# SCH_n2_power_distribution_board-png_2022.net
KiCad netlist of a schematic drawn in EasyEDA
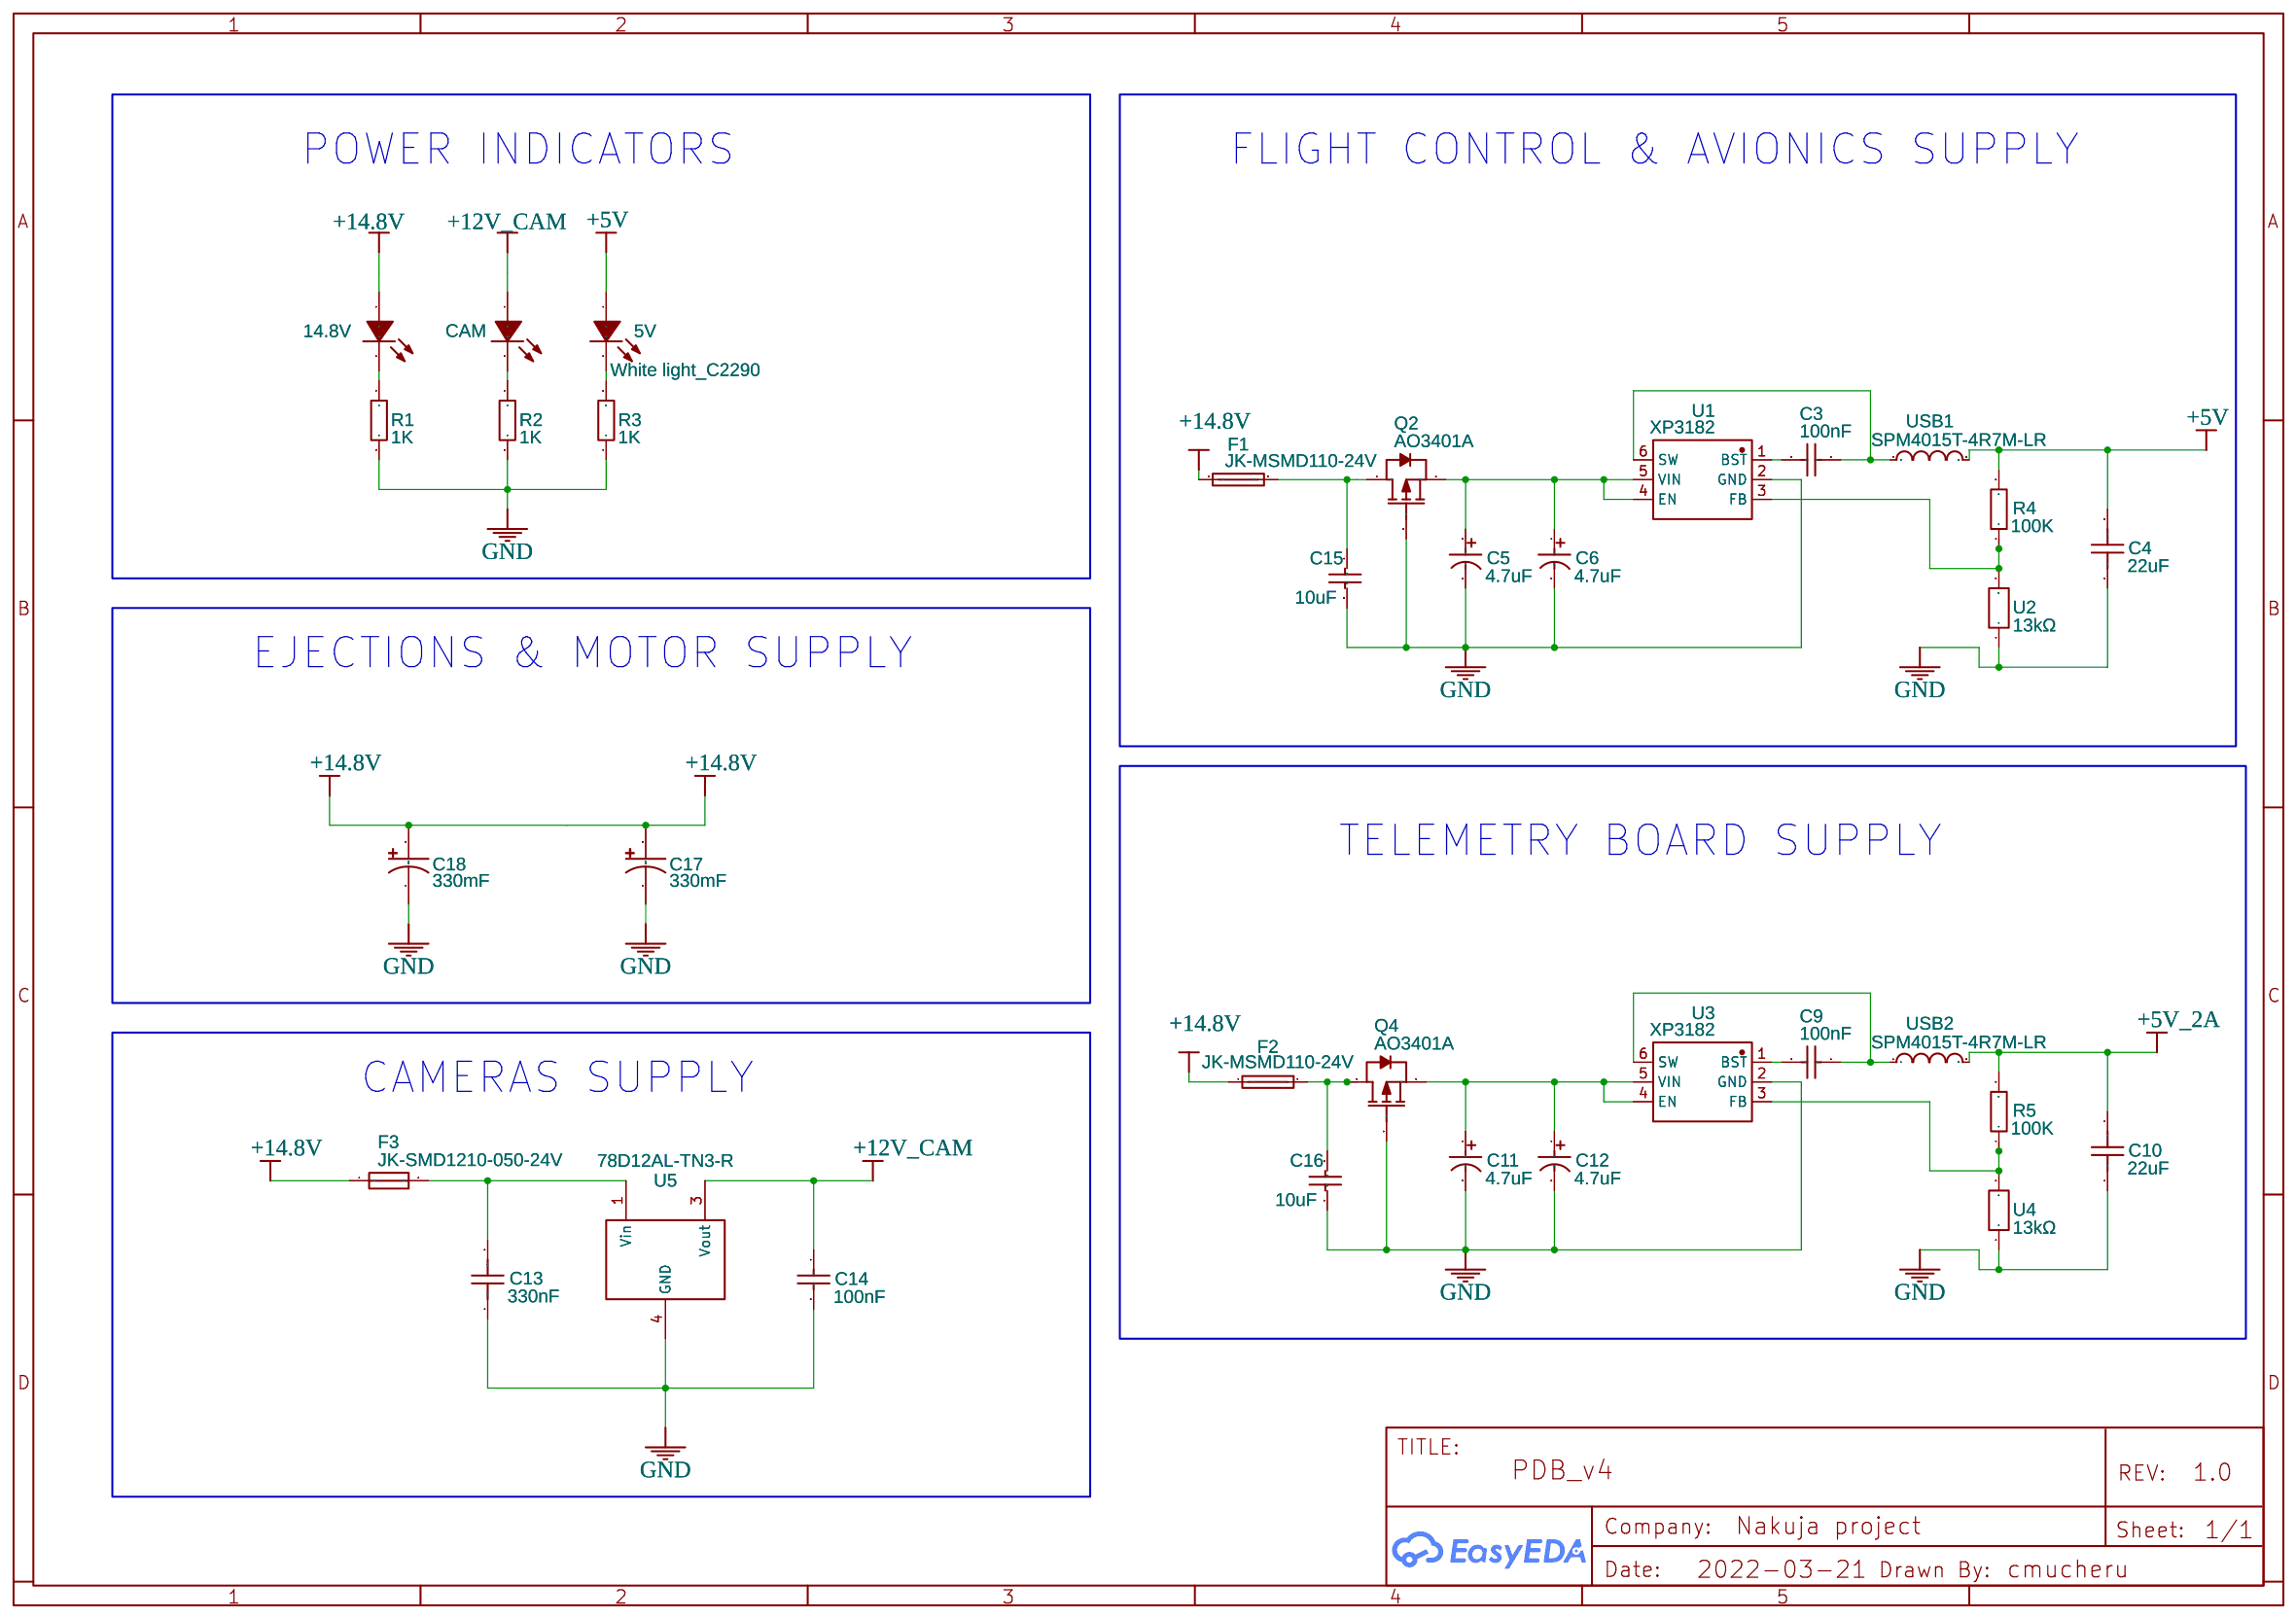
[diagram p0: PDB]
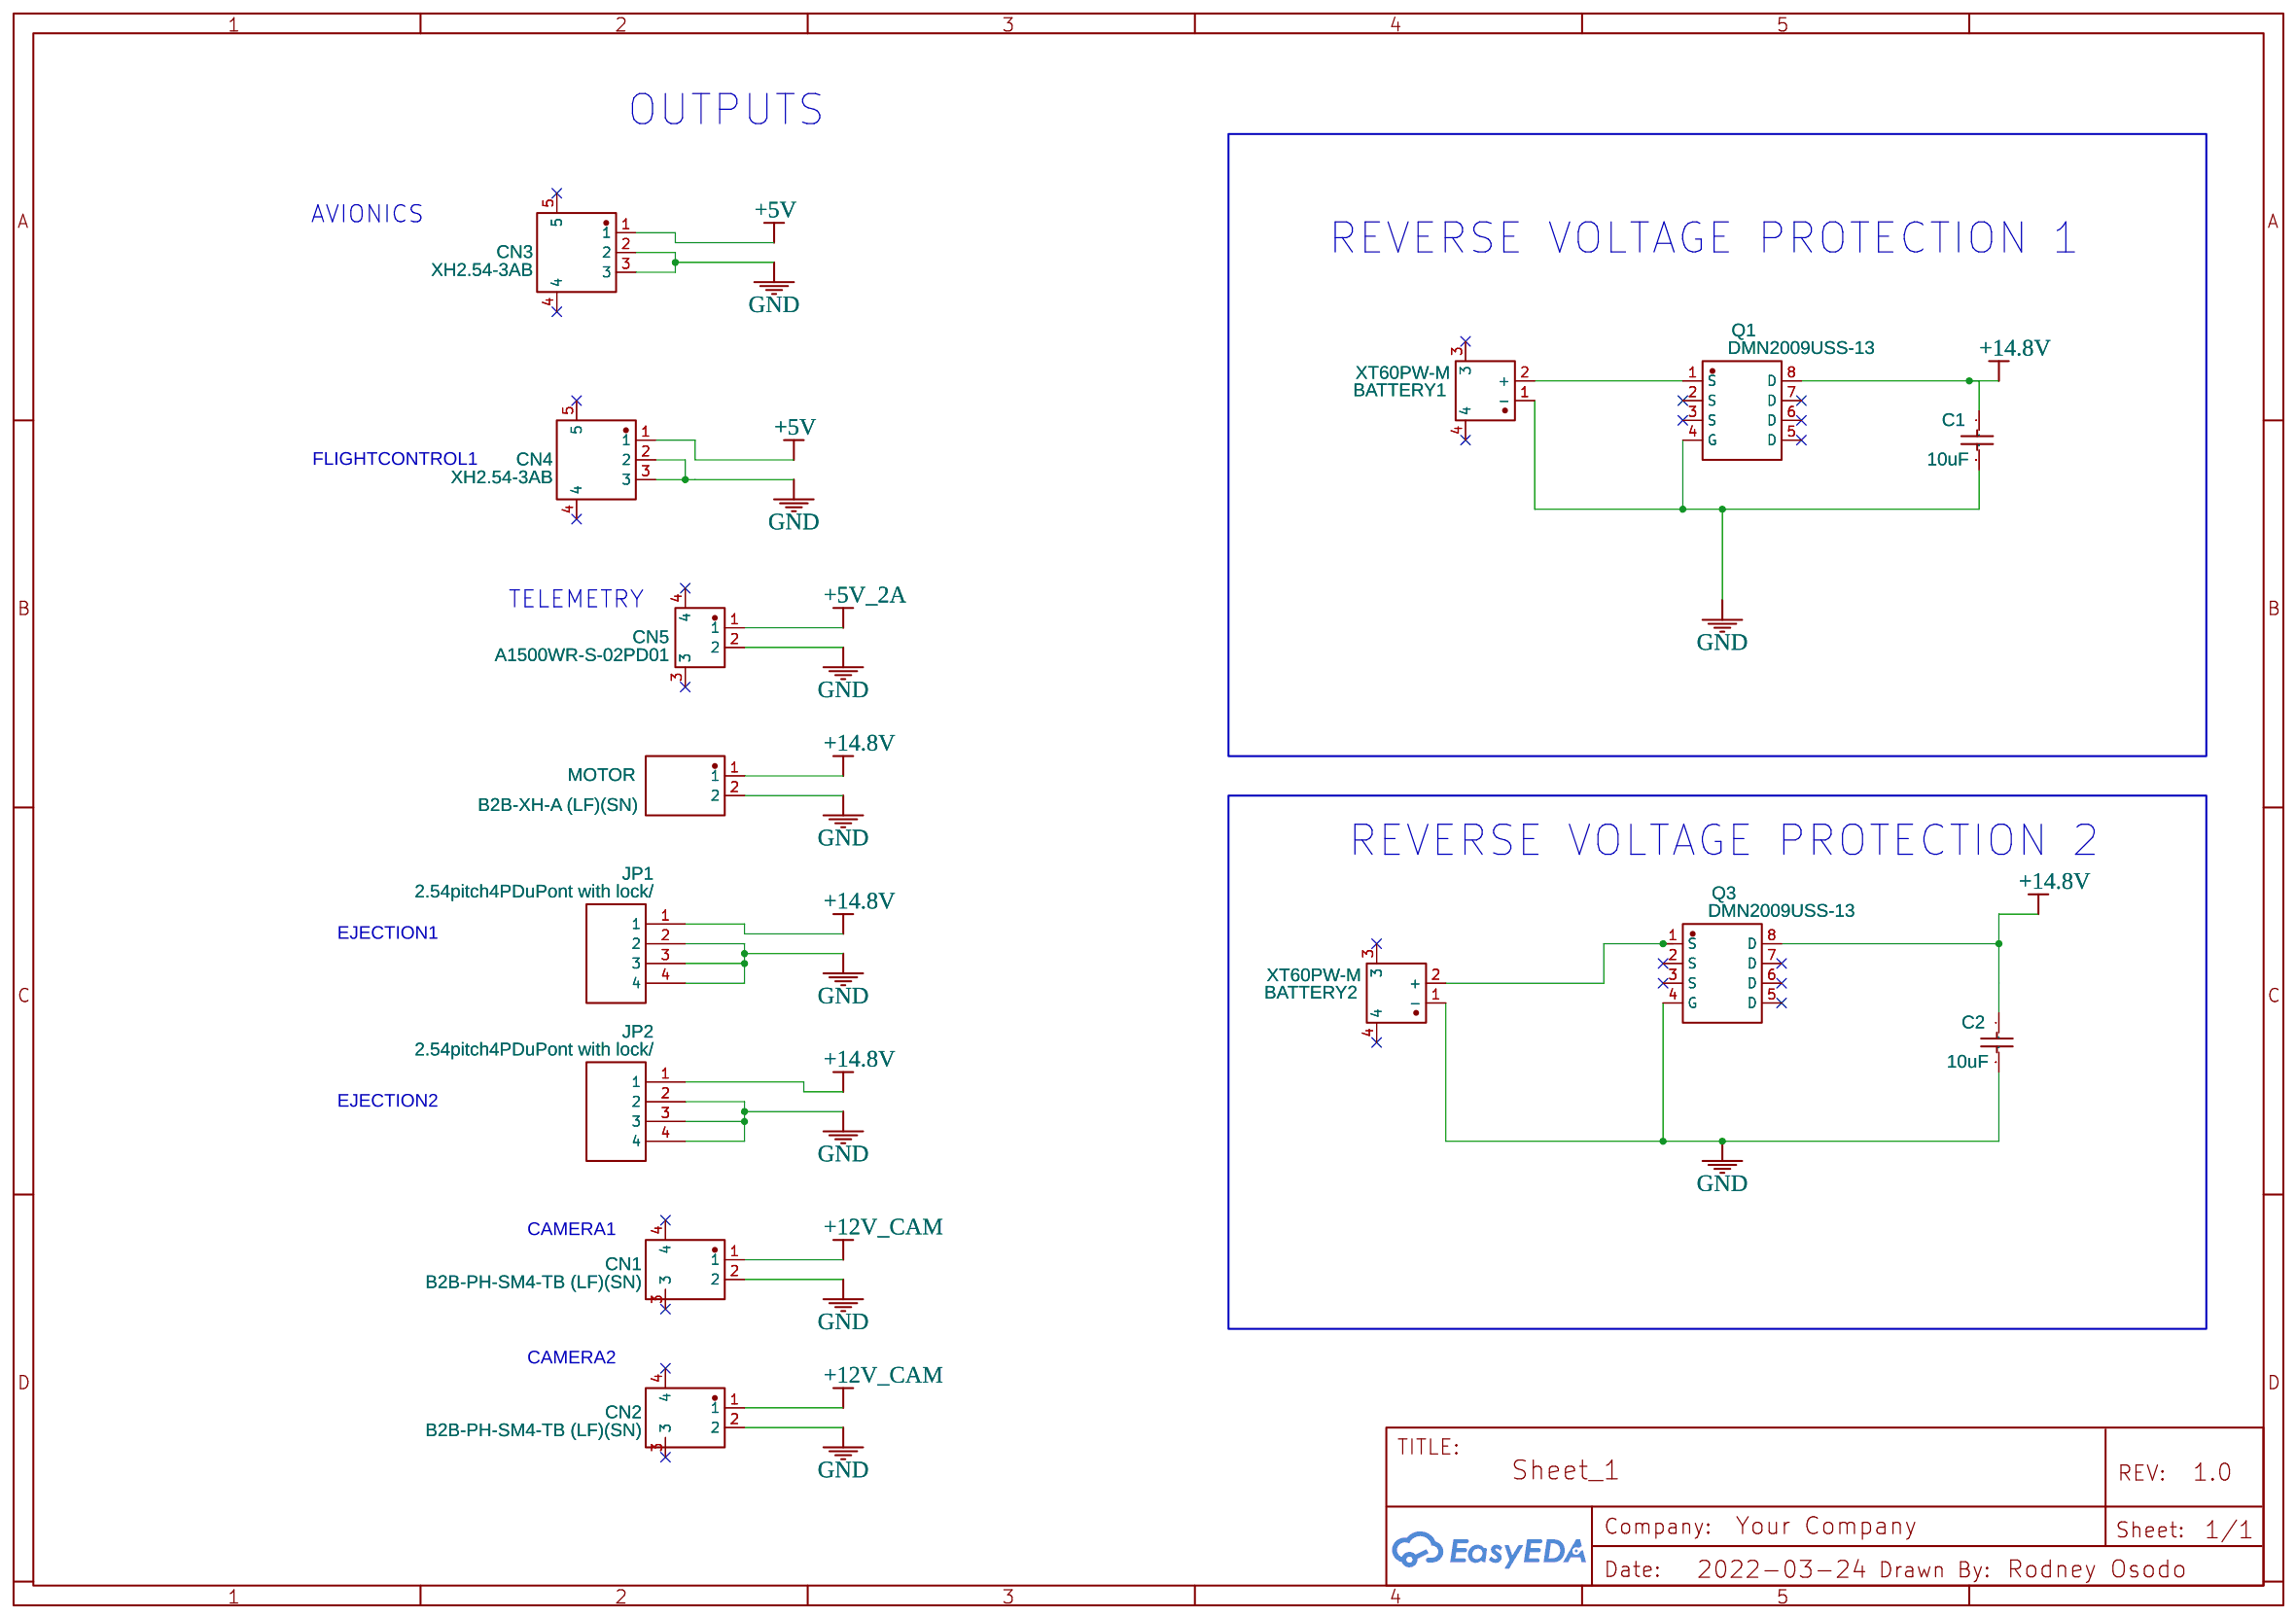
[diagram p1: Connectors]

(export (version "E")
  (design (tool "Eeschema 10.0.6"))
  (components
    (comp (ref "5V")
      (value "White light_C2290")
      (fields
        (field (name "BOM_Manufacturer Part") "0603White light")
        (field (name "BOM_Supplier Part") "C2290")
      )
      (libsource (lib "") (part "0603White light_C2290_1"))
    )
    (comp (ref "14.8V")
      (value "White light_C2290")
      (fields
        (field (name "BOM_Manufacturer Part") "0603White light")
        (field (name "BOM_Supplier Part") "C2290")
      )
      (libsource (lib "") (part "0603White light_C2290_2"))
    )
    (comp (ref "C3")
      (value "100nF")
      (fields
        (field (name "BOM_Manufacturer Part") "CL05B104KO5NNNC")
        (field (name "BOM_Supplier Part") "C1525")
      )
      (libsource (lib "") (part "CL05B104KO5NNNC_1"))
    )
    (comp (ref "C4")
      (value "22uF")
      (fields
        (field (name "BOM_Manufacturer Part") "GRM155R60J226ME11D")
        (field (name "BOM_Supplier Part") "C415703")
      )
      (libsource (lib "") (part "GRM155R60J226ME11D"))
    )
    (comp (ref "C5")
      (value "4.7uF")
      (fields
        (field (name "BOM_Manufacturer Part") "RVT1V4R7M0405")
        (field (name "BOM_Supplier Part") "C72511")
      )
      (libsource (lib "") (part "RVT1V4R7M0405"))
    )
    (comp (ref "C6")
      (value "4.7uF")
      (fields
        (field (name "BOM_Manufacturer Part") "RVT1V4R7M0405")
        (field (name "BOM_Supplier Part") "C72511")
      )
      (libsource (lib "") (part "RVT1V4R7M0405"))
    )
    (comp (ref "C9")
      (value "100nF")
      (fields
        (field (name "BOM_Manufacturer Part") "CL05B104KO5NNNC")
        (field (name "BOM_Supplier Part") "C1525")
      )
      (libsource (lib "") (part "CL05B104KO5NNNC_1"))
    )
    (comp (ref "C10")
      (value "22uF")
      (fields
        (field (name "BOM_Manufacturer Part") "GRM155R60J226ME11D")
        (field (name "BOM_Supplier Part") "C415703")
      )
      (libsource (lib "") (part "GRM155R60J226ME11D"))
    )
    (comp (ref "C11")
      (value "4.7uF")
      (fields
        (field (name "BOM_Manufacturer Part") "RVT1V4R7M0405")
        (field (name "BOM_Supplier Part") "C72511")
      )
      (libsource (lib "") (part "RVT1V4R7M0405"))
    )
    (comp (ref "C12")
      (value "4.7uF")
      (fields
        (field (name "BOM_Manufacturer Part") "RVT1V4R7M0405")
        (field (name "BOM_Supplier Part") "C72511")
      )
      (libsource (lib "") (part "RVT1V4R7M0405"))
    )
    (comp (ref "C13")
      (value "330nF")
      (fields
        (field (name "BOM_Manufacturer Part") "CC0402ZRY5V7BB334")
        (field (name "BOM_Supplier Part") "C527033")
      )
      (libsource (lib "") (part "CC0402ZRY5V7BB334"))
    )
    (comp (ref "C14")
      (value "100nF")
      (fields
        (field (name "BOM_Manufacturer Part") "CL05B104KO5NNNC")
        (field (name "BOM_Supplier Part") "C1525")
      )
      (libsource (lib "") (part "CL05B104KO5NNNC"))
    )
    (comp (ref "C15")
      (value "10uF")
      (fields
        (field (name "BOM_Manufacturer Part") "CL05A106MQ5NUNC")
        (field (name "BOM_Supplier Part") "C15525")
      )
      (libsource (lib "") (part "CL05A106MQ5NUNC"))
    )
    (comp (ref "C16")
      (value "10uF")
      (fields
        (field (name "BOM_Manufacturer Part") "CL05A106MQ5NUNC")
        (field (name "BOM_Supplier Part") "C15525")
      )
      (libsource (lib "") (part "CL05A106MQ5NUNC"))
    )
    (comp (ref "C17")
      (value "330mF")
      (fields
        (field (name "BOM_Manufacturer Part") "EECS0HD334H")
        (field (name "BOM_Supplier Part") "C128528")
      )
      (libsource (lib "") (part "EECS0HD334H_1"))
    )
    (comp (ref "C18")
      (value "330mF")
      (fields
        (field (name "BOM_Manufacturer Part") "EECS0HD334H")
        (field (name "BOM_Supplier Part") "C128528")
      )
      (libsource (lib "") (part "EECS0HD334H"))
    )
    (comp (ref "CAM")
      (value "White light_C2290")
      (fields
        (field (name "BOM_Manufacturer Part") "0603White light")
        (field (name "BOM_Supplier Part") "C2290")
      )
      (libsource (lib "") (part "0603White light_C2290"))
    )
    (comp (ref "F1")
      (value "JK-MSMD110-24V")
      (fields (field (name "BOM_Supplier Part") "C369172"))
      (libsource (lib "") (part "JK-MSMD110-24V"))
    )
    (comp (ref "F2")
      (value "JK-MSMD110-24V")
      (fields (field (name "BOM_Supplier Part") "C369172"))
      (libsource (lib "") (part "JK-MSMD110-24V"))
    )
    (comp (ref "F3")
      (value "JK-SMD1210-050-24V")
      (fields (field (name "BOM_Supplier Part") "C720078"))
      (libsource (lib "") (part "JK-SMD1210-050-24V"))
    )
    (comp (ref "Q2")
      (value "AO3401A")
      (fields (field (name "BOM_Supplier Part") "C15127"))
      (libsource (lib "") (part "AO3401A"))
    )
    (comp (ref "Q4")
      (value "AO3401A")
      (fields (field (name "BOM_Supplier Part") "C15127"))
      (libsource (lib "") (part "AO3401A"))
    )
    (comp (ref "R1")
      (value "1K")
      (fields
        (field (name "BOM_Manufacturer Part") "0402WGF5101TCE")
        (field (name "BOM_Supplier Part") "C25905")
      )
      (libsource (lib "") (part "0402WGF5101TCE_1"))
    )
    (comp (ref "R2")
      (value "1K")
      (fields
        (field (name "BOM_Manufacturer Part") "0402WGF5101TCE")
        (field (name "BOM_Supplier Part") "C25905")
      )
      (libsource (lib "") (part "0402WGF5101TCE_1"))
    )
    (comp (ref "R3")
      (value "1K")
      (fields
        (field (name "BOM_Manufacturer Part") "0402WGF5101TCE")
        (field (name "BOM_Supplier Part") "C25905")
      )
      (libsource (lib "") (part "0402WGF5101TCE"))
    )
    (comp (ref "R4")
      (value "100K")
      (fields
        (field (name "BOM_Manufacturer Part") "0402WGF1003TCE")
        (field (name "BOM_Supplier Part") "C25741")
      )
      (libsource (lib "") (part "0402WGF1003TCE"))
    )
    (comp (ref "R5")
      (value "100K")
      (fields
        (field (name "BOM_Manufacturer Part") "0402WGF1003TCE")
        (field (name "BOM_Supplier Part") "C25741")
      )
      (libsource (lib "") (part "0402WGF1003TCE"))
    )
    (comp (ref "U1")
      (value "XP3182")
      (fields (field (name "BOM_Supplier Part") "C2802261"))
      (libsource (lib "") (part "XP3182"))
    )
    (comp (ref "U2")
      (value "13kΩ")
      (fields
        (field (name "BOM_Manufacturer Part") "PTFR0402B13K0P9")
        (field (name "BOM_Supplier Part") "C2693072")
      )
      (libsource (lib "") (part "PTFR0402B13K0P9"))
    )
    (comp (ref "U3")
      (value "XP3182")
      (fields (field (name "BOM_Supplier Part") "C2802261"))
      (libsource (lib "") (part "XP3182"))
    )
    (comp (ref "U4")
      (value "13kΩ")
      (fields
        (field (name "BOM_Manufacturer Part") "PTFR0402B13K0P9")
        (field (name "BOM_Supplier Part") "C2693072")
      )
      (libsource (lib "") (part "PTFR0402B13K0P9"))
    )
    (comp (ref "U5")
      (value "78D12AL-TN3-R")
      (fields (field (name "BOM_Supplier Part") "C73290"))
      (libsource (lib "") (part "78D12AL-TN3-R"))
    )
    (comp (ref "USB1")
      (value "SPM4015T-4R7M-LR")
      (fields (field (name "BOM_Supplier Part") "C2052599"))
      (libsource (lib "") (part "SPM4015T-4R7M-LR"))
    )
    (comp (ref "USB2")
      (value "SPM4015T-4R7M-LR")
      (fields (field (name "BOM_Supplier Part") "C2052599"))
      (libsource (lib "") (part "SPM4015T-4R7M-LR"))
    )
    (comp (ref "BATTERY1")
      (value "XT60PW-M")
      (fields (field (name "BOM_Supplier Part") "C98732"))
      (libsource (lib "") (part "XT60PW-M"))
    )
    (comp (ref "BATTERY2")
      (value "XT60PW-M")
      (fields (field (name "BOM_Supplier Part") "C98732"))
      (libsource (lib "") (part "XT60PW-M"))
    )
    (comp (ref "C1")
      (value "10uF")
      (fields
        (field (name "BOM_Manufacturer Part") "CL05A106MQ5NUNC")
        (field (name "BOM_Supplier Part") "C15525")
      )
      (libsource (lib "") (part "CL05A106MQ5NUNC"))
    )
    (comp (ref "C2")
      (value "10uF")
      (fields
        (field (name "BOM_Manufacturer Part") "CL05A106MQ5NUNC")
        (field (name "BOM_Supplier Part") "C15525")
      )
      (libsource (lib "") (part "CL05A106MQ5NUNC"))
    )
    (comp (ref "CN1")
      (value "B2B-PH-SM4-TB (LF)(SN)")
      (fields (field (name "BOM_Supplier Part") "C160352"))
      (libsource (lib "") (part "B2B-PH-SM4-TB (LF)(SN)"))
    )
    (comp (ref "CN2")
      (value "B2B-PH-SM4-TB (LF)(SN)")
      (fields (field (name "BOM_Supplier Part") "C160352"))
      (libsource (lib "") (part "B2B-PH-SM4-TB (LF)(SN)"))
    )
    (comp (ref "CN3")
      (value "XH2.54-3AB")
      (fields (field (name "BOM_Supplier Part") "C146126"))
      (libsource (lib "") (part "XH2.54-3AB"))
    )
    (comp (ref "CN4")
      (value "XH2.54-3AB")
      (fields (field (name "BOM_Supplier Part") "C146126"))
      (libsource (lib "") (part "XH2.54-3AB"))
    )
    (comp (ref "CN5")
      (value "A1500WR-S-02PD01")
      (fields (field (name "BOM_Supplier Part") "C360106"))
      (libsource (lib "") (part "A1500WR-S-02PD01"))
    )
    (comp (ref "JP1")
      (value "2.54pitch4PDuPont with lock/")
      (fields (field (name "BOM_Supplier Part") "C41927"))
      (libsource (lib "") (part "2.54pitch4PDuPont with lock/"))
    )
    (comp (ref "JP2")
      (value "2.54pitch4PDuPont with lock/")
      (fields (field (name "BOM_Supplier Part") "C41927"))
      (libsource (lib "") (part "2.54pitch4PDuPont with lock/"))
    )
    (comp (ref "MOTOR")
      (value "B2B-XH-A (LF)(SN)")
      (fields (field (name "BOM_Supplier Part") "C158012"))
      (libsource (lib "") (part "B2B-XH-A (LF)(SN)"))
    )
    (comp (ref "Q1")
      (value "DMN2009USS-13")
      (fields (field (name "BOM_Supplier Part") "C460995"))
      (libsource (lib "") (part "DMN2009USS-13"))
    )
    (comp (ref "Q3")
      (value "DMN2009USS-13")
      (fields (field (name "BOM_Supplier Part") "C460995"))
      (libsource (lib "") (part "DMN2009USS-13"))
    )
  )
  (nets
    (net (code "1") (name "+5V") (class "Default")
      (node (ref "5V") (pin "1") (pinfunction "A_1") (pintype "unspecified"))
      (node (ref "C4") (pin "2") (pinfunction "2_2") (pintype "unspecified"))
      (node (ref "CN3") (pin "1") (pinfunction "1_1") (pintype "unspecified"))
      (node (ref "CN4") (pin "1") (pinfunction "1_1") (pintype "unspecified"))
      (node (ref "R4") (pin "2") (pinfunction "2_2") (pintype "input"))
      (node (ref "USB1") (pin "2") (pinfunction "2_2") (pintype "unspecified"))
    )
    (net (code "2") (name "+5V_2A") (class "Default")
      (node (ref "C10") (pin "2") (pinfunction "2_2") (pintype "unspecified"))
      (node (ref "CN5") (pin "1") (pinfunction "1_1") (pintype "unspecified"))
      (node (ref "R5") (pin "2") (pinfunction "2_2") (pintype "input"))
      (node (ref "USB2") (pin "2") (pinfunction "2_2") (pintype "unspecified"))
    )
    (net (code "3") (name "+12V_CAM") (class "Default")
      (node (ref "C14") (pin "1") (pinfunction "1_1") (pintype "input"))
      (node (ref "CAM") (pin "1") (pinfunction "A_1") (pintype "unspecified"))
      (node (ref "CN1") (pin "1") (pinfunction "1_1") (pintype "unspecified"))
      (node (ref "CN2") (pin "1") (pinfunction "1_1") (pintype "unspecified"))
      (node (ref "U5") (pin "3") (pinfunction "Vout_3") (pintype "unspecified"))
    )
    (net (code "4") (name "+14.8V") (class "Default")
      (node (ref "14.8V") (pin "1") (pinfunction "A_1") (pintype "unspecified"))
      (node (ref "C1") (pin "1") (pinfunction "1_1") (pintype "input"))
      (node (ref "C17") (pin "1") (pinfunction "1_1") (pintype "unspecified"))
      (node (ref "C18") (pin "1") (pinfunction "1_1") (pintype "unspecified"))
      (node (ref "C2") (pin "1") (pinfunction "1_1") (pintype "input"))
      (node (ref "F1") (pin "1") (pinfunction "1_1") (pintype "unspecified"))
      (node (ref "F2") (pin "1") (pinfunction "1_1") (pintype "unspecified"))
      (node (ref "F3") (pin "1") (pinfunction "1_1") (pintype "unspecified"))
      (node (ref "JP1") (pin "1") (pinfunction "1_1") (pintype "unspecified"))
      (node (ref "JP2") (pin "1") (pinfunction "1_1") (pintype "unspecified"))
      (node (ref "MOTOR") (pin "1") (pinfunction "1_1") (pintype "unspecified"))
      (node (ref "Q1") (pin "8") (pinfunction "D_8") (pintype "unspecified"))
      (node (ref "Q3") (pin "8") (pinfunction "D_8") (pintype "unspecified"))
    )
    (net (code "5") (name "GND") (class "Default")
      (node (ref "BATTERY1") (pin "1") (pinfunction "-_1") (pintype "unspecified"))
      (node (ref "BATTERY2") (pin "1") (pinfunction "-_1") (pintype "unspecified"))
      (node (ref "C1") (pin "2") (pinfunction "2_2") (pintype "input"))
      (node (ref "C10") (pin "1") (pinfunction "1_1") (pintype "unspecified"))
      (node (ref "C11") (pin "2") (pinfunction "2_2") (pintype "input"))
      (node (ref "C12") (pin "2") (pinfunction "2_2") (pintype "input"))
      (node (ref "C13") (pin "1") (pinfunction "1_1") (pintype "unspecified"))
      (node (ref "C14") (pin "2") (pinfunction "2_2") (pintype "input"))
      (node (ref "C15") (pin "2") (pinfunction "2_2") (pintype "input"))
      (node (ref "C16") (pin "2") (pinfunction "2_2") (pintype "input"))
      (node (ref "C17") (pin "2") (pinfunction "2_2") (pintype "unspecified"))
      (node (ref "C18") (pin "2") (pinfunction "2_2") (pintype "unspecified"))
      (node (ref "C2") (pin "2") (pinfunction "2_2") (pintype "input"))
      (node (ref "C4") (pin "1") (pinfunction "1_1") (pintype "unspecified"))
      (node (ref "C5") (pin "2") (pinfunction "2_2") (pintype "input"))
      (node (ref "C6") (pin "2") (pinfunction "2_2") (pintype "input"))
      (node (ref "CN1") (pin "2") (pinfunction "2_2") (pintype "unspecified"))
      (node (ref "CN2") (pin "2") (pinfunction "2_2") (pintype "unspecified"))
      (node (ref "CN3") (pin "2") (pinfunction "2_2") (pintype "unspecified"))
      (node (ref "CN3") (pin "3") (pinfunction "3_3") (pintype "unspecified"))
      (node (ref "CN4") (pin "2") (pinfunction "2_2") (pintype "unspecified"))
      (node (ref "CN4") (pin "3") (pinfunction "3_3") (pintype "unspecified"))
      (node (ref "CN5") (pin "2") (pinfunction "2_2") (pintype "unspecified"))
      (node (ref "JP1") (pin "2") (pinfunction "2_2") (pintype "unspecified"))
      (node (ref "JP1") (pin "3") (pinfunction "3_3") (pintype "unspecified"))
      (node (ref "JP1") (pin "4") (pinfunction "4_4") (pintype "unspecified"))
      (node (ref "JP2") (pin "2") (pinfunction "2_2") (pintype "unspecified"))
      (node (ref "JP2") (pin "3") (pinfunction "3_3") (pintype "unspecified"))
      (node (ref "JP2") (pin "4") (pinfunction "4_4") (pintype "unspecified"))
      (node (ref "MOTOR") (pin "2") (pinfunction "2_2") (pintype "unspecified"))
      (node (ref "Q1") (pin "4") (pinfunction "G_4") (pintype "unspecified"))
      (node (ref "Q2") (pin "1") (pinfunction "G_1") (pintype "unspecified"))
      (node (ref "Q3") (pin "4") (pinfunction "G_4") (pintype "unspecified"))
      (node (ref "Q4") (pin "1") (pinfunction "G_1") (pintype "unspecified"))
      (node (ref "R1") (pin "2") (pinfunction "2_2") (pintype "input"))
      (node (ref "R2") (pin "2") (pinfunction "2_2") (pintype "input"))
      (node (ref "R3") (pin "1") (pinfunction "1_1") (pintype "input"))
      (node (ref "U1") (pin "2") (pinfunction "GND_2") (pintype "unspecified"))
      (node (ref "U2") (pin "1") (pinfunction "1_1") (pintype "unspecified"))
      (node (ref "U3") (pin "2") (pinfunction "GND_2") (pintype "unspecified"))
      (node (ref "U4") (pin "1") (pinfunction "1_1") (pintype "unspecified"))
      (node (ref "U5") (pin "4") (pinfunction "GND_4") (pintype "unspecified"))
    )
    (net (code "6") (name "Net-(5V-K)") (class "Default")
      (node (ref "5V") (pin "2") (pinfunction "K_2") (pintype "unspecified"))
      (node (ref "R3") (pin "2") (pinfunction "2_2") (pintype "input"))
    )
    (net (code "7") (name "Net-(14.8V-K)") (class "Default")
      (node (ref "14.8V") (pin "2") (pinfunction "K_2") (pintype "unspecified"))
      (node (ref "R1") (pin "1") (pinfunction "1_1") (pintype "input"))
    )
    (net (code "8") (name "Net-(BATTERY1-+)") (class "Default")
      (node (ref "BATTERY1") (pin "2") (pinfunction "+_2") (pintype "unspecified"))
      (node (ref "Q1") (pin "1") (pinfunction "S_1") (pintype "unspecified"))
    )
    (net (code "9") (name "Net-(BATTERY2-+)") (class "Default")
      (node (ref "BATTERY2") (pin "2") (pinfunction "+_2") (pintype "unspecified"))
      (node (ref "Q3") (pin "1") (pinfunction "S_1") (pintype "unspecified"))
    )
    (net (code "10") (name "Net-(CAM-K)") (class "Default")
      (node (ref "CAM") (pin "2") (pinfunction "K_2") (pintype "unspecified"))
      (node (ref "R2") (pin "1") (pinfunction "1_1") (pintype "input"))
    )
    (net (code "11") (name "Net-(Q2-D)") (class "Default")
      (node (ref "C15") (pin "1") (pinfunction "1_1") (pintype "input"))
      (node (ref "F1") (pin "2") (pinfunction "2_2") (pintype "unspecified"))
      (node (ref "Q2") (pin "3") (pinfunction "D_3") (pintype "unspecified"))
    )
    (net (code "12") (name "Net-(Q2-S)") (class "Default")
      (node (ref "C5") (pin "1") (pinfunction "1_1") (pintype "input"))
      (node (ref "C6") (pin "1") (pinfunction "1_1") (pintype "input"))
      (node (ref "Q2") (pin "2") (pinfunction "S_2") (pintype "unspecified"))
      (node (ref "U1") (pin "4") (pinfunction "EN_4") (pintype "unspecified"))
      (node (ref "U1") (pin "5") (pinfunction "VIN_5") (pintype "unspecified"))
    )
    (net (code "13") (name "Net-(Q4-D)") (class "Default")
      (node (ref "C16") (pin "1") (pinfunction "1_1") (pintype "input"))
      (node (ref "F2") (pin "2") (pinfunction "2_2") (pintype "unspecified"))
      (node (ref "Q4") (pin "3") (pinfunction "D_3") (pintype "unspecified"))
    )
    (net (code "14") (name "Net-(Q4-S)") (class "Default")
      (node (ref "C11") (pin "1") (pinfunction "1_1") (pintype "input"))
      (node (ref "C12") (pin "1") (pinfunction "1_1") (pintype "input"))
      (node (ref "Q4") (pin "2") (pinfunction "S_2") (pintype "unspecified"))
      (node (ref "U3") (pin "4") (pinfunction "EN_4") (pintype "unspecified"))
      (node (ref "U3") (pin "5") (pinfunction "VIN_5") (pintype "unspecified"))
    )
    (net (code "15") (name "Net-(U1-BST)") (class "Default")
      (node (ref "C3") (pin "2") (pinfunction "2_2") (pintype "input"))
      (node (ref "U1") (pin "1") (pinfunction "BST_1") (pintype "unspecified"))
    )
    (net (code "16") (name "Net-(U1-FB)") (class "Default")
      (node (ref "R4") (pin "1") (pinfunction "1_1") (pintype "input"))
      (node (ref "U1") (pin "3") (pinfunction "FB_3") (pintype "unspecified"))
      (node (ref "U2") (pin "2") (pinfunction "2_2") (pintype "unspecified"))
    )
    (net (code "17") (name "Net-(U1-SW)") (class "Default")
      (node (ref "C3") (pin "1") (pinfunction "1_1") (pintype "input"))
      (node (ref "U1") (pin "6") (pinfunction "SW_6") (pintype "unspecified"))
      (node (ref "USB1") (pin "1") (pinfunction "1_1") (pintype "unspecified"))
    )
    (net (code "18") (name "Net-(U3-BST)") (class "Default")
      (node (ref "C9") (pin "2") (pinfunction "2_2") (pintype "input"))
      (node (ref "U3") (pin "1") (pinfunction "BST_1") (pintype "unspecified"))
    )
    (net (code "19") (name "Net-(U3-FB)") (class "Default")
      (node (ref "R5") (pin "1") (pinfunction "1_1") (pintype "input"))
      (node (ref "U3") (pin "3") (pinfunction "FB_3") (pintype "unspecified"))
      (node (ref "U4") (pin "2") (pinfunction "2_2") (pintype "unspecified"))
    )
    (net (code "20") (name "Net-(U3-SW)") (class "Default")
      (node (ref "C9") (pin "1") (pinfunction "1_1") (pintype "input"))
      (node (ref "U3") (pin "6") (pinfunction "SW_6") (pintype "unspecified"))
      (node (ref "USB2") (pin "1") (pinfunction "1_1") (pintype "unspecified"))
    )
    (net (code "21") (name "Net-(U5-Vin)") (class "Default")
      (node (ref "C13") (pin "2") (pinfunction "2_2") (pintype "unspecified"))
      (node (ref "F3") (pin "2") (pinfunction "2_2") (pintype "unspecified"))
      (node (ref "U5") (pin "1") (pinfunction "Vin_1") (pintype "unspecified"))
    )
    (net (code "22") (name "unconnected-(BATTERY1-Pad3)") (class "Default")
      (node (ref "BATTERY1") (pin "3") (pinfunction "3_3") (pintype "unspecified+no_connect"))
    )
    (net (code "23") (name "unconnected-(BATTERY1-Pad4)") (class "Default")
      (node (ref "BATTERY1") (pin "4") (pinfunction "4_4") (pintype "unspecified+no_connect"))
    )
    (net (code "24") (name "unconnected-(BATTERY2-Pad3)") (class "Default")
      (node (ref "BATTERY2") (pin "3") (pinfunction "3_3") (pintype "unspecified+no_connect"))
    )
    (net (code "25") (name "unconnected-(BATTERY2-Pad4)") (class "Default")
      (node (ref "BATTERY2") (pin "4") (pinfunction "4_4") (pintype "unspecified+no_connect"))
    )
    (net (code "26") (name "unconnected-(CN1-Pad3)") (class "Default")
      (node (ref "CN1") (pin "3") (pinfunction "3_3") (pintype "unspecified+no_connect"))
    )
    (net (code "27") (name "unconnected-(CN1-Pad4)") (class "Default")
      (node (ref "CN1") (pin "4") (pinfunction "4_4") (pintype "unspecified+no_connect"))
    )
    (net (code "28") (name "unconnected-(CN2-Pad3)") (class "Default")
      (node (ref "CN2") (pin "3") (pinfunction "3_3") (pintype "unspecified+no_connect"))
    )
    (net (code "29") (name "unconnected-(CN2-Pad4)") (class "Default")
      (node (ref "CN2") (pin "4") (pinfunction "4_4") (pintype "unspecified+no_connect"))
    )
    (net (code "30") (name "unconnected-(CN3-Pad4)") (class "Default")
      (node (ref "CN3") (pin "4") (pinfunction "4_4") (pintype "unspecified+no_connect"))
    )
    (net (code "31") (name "unconnected-(CN3-Pad5)") (class "Default")
      (node (ref "CN3") (pin "5") (pinfunction "5_5") (pintype "unspecified+no_connect"))
    )
    (net (code "32") (name "unconnected-(CN4-Pad4)") (class "Default")
      (node (ref "CN4") (pin "4") (pinfunction "4_4") (pintype "unspecified+no_connect"))
    )
    (net (code "33") (name "unconnected-(CN4-Pad5)") (class "Default")
      (node (ref "CN4") (pin "5") (pinfunction "5_5") (pintype "unspecified+no_connect"))
    )
    (net (code "34") (name "unconnected-(CN5-Pad3)") (class "Default")
      (node (ref "CN5") (pin "3") (pinfunction "3_3") (pintype "unspecified+no_connect"))
    )
    (net (code "35") (name "unconnected-(CN5-Pad4)") (class "Default")
      (node (ref "CN5") (pin "4") (pinfunction "4_4") (pintype "unspecified+no_connect"))
    )
    (net (code "36") (name "unconnected-(Q1-D-Pad5)") (class "Default")
      (node (ref "Q1") (pin "5") (pinfunction "D_5") (pintype "unspecified+no_connect"))
    )
    (net (code "37") (name "unconnected-(Q1-D-Pad6)") (class "Default")
      (node (ref "Q1") (pin "6") (pinfunction "D_6") (pintype "unspecified+no_connect"))
    )
    (net (code "38") (name "unconnected-(Q1-D-Pad7)") (class "Default")
      (node (ref "Q1") (pin "7") (pinfunction "D_7") (pintype "unspecified+no_connect"))
    )
    (net (code "39") (name "unconnected-(Q1-S-Pad2)") (class "Default")
      (node (ref "Q1") (pin "2") (pinfunction "S_2") (pintype "unspecified+no_connect"))
    )
    (net (code "40") (name "unconnected-(Q1-S-Pad3)") (class "Default")
      (node (ref "Q1") (pin "3") (pinfunction "S_3") (pintype "unspecified+no_connect"))
    )
    (net (code "41") (name "unconnected-(Q3-D-Pad5)") (class "Default")
      (node (ref "Q3") (pin "5") (pinfunction "D_5") (pintype "unspecified+no_connect"))
    )
    (net (code "42") (name "unconnected-(Q3-D-Pad6)") (class "Default")
      (node (ref "Q3") (pin "6") (pinfunction "D_6") (pintype "unspecified+no_connect"))
    )
    (net (code "43") (name "unconnected-(Q3-D-Pad7)") (class "Default")
      (node (ref "Q3") (pin "7") (pinfunction "D_7") (pintype "unspecified+no_connect"))
    )
    (net (code "44") (name "unconnected-(Q3-S-Pad2)") (class "Default")
      (node (ref "Q3") (pin "2") (pinfunction "S_2") (pintype "unspecified+no_connect"))
    )
    (net (code "45") (name "unconnected-(Q3-S-Pad3)") (class "Default")
      (node (ref "Q3") (pin "3") (pinfunction "S_3") (pintype "unspecified+no_connect"))
    )
  )
)
